# CPU_v1_0.net
KiCad netlist of a schematic drawn in EAGLE
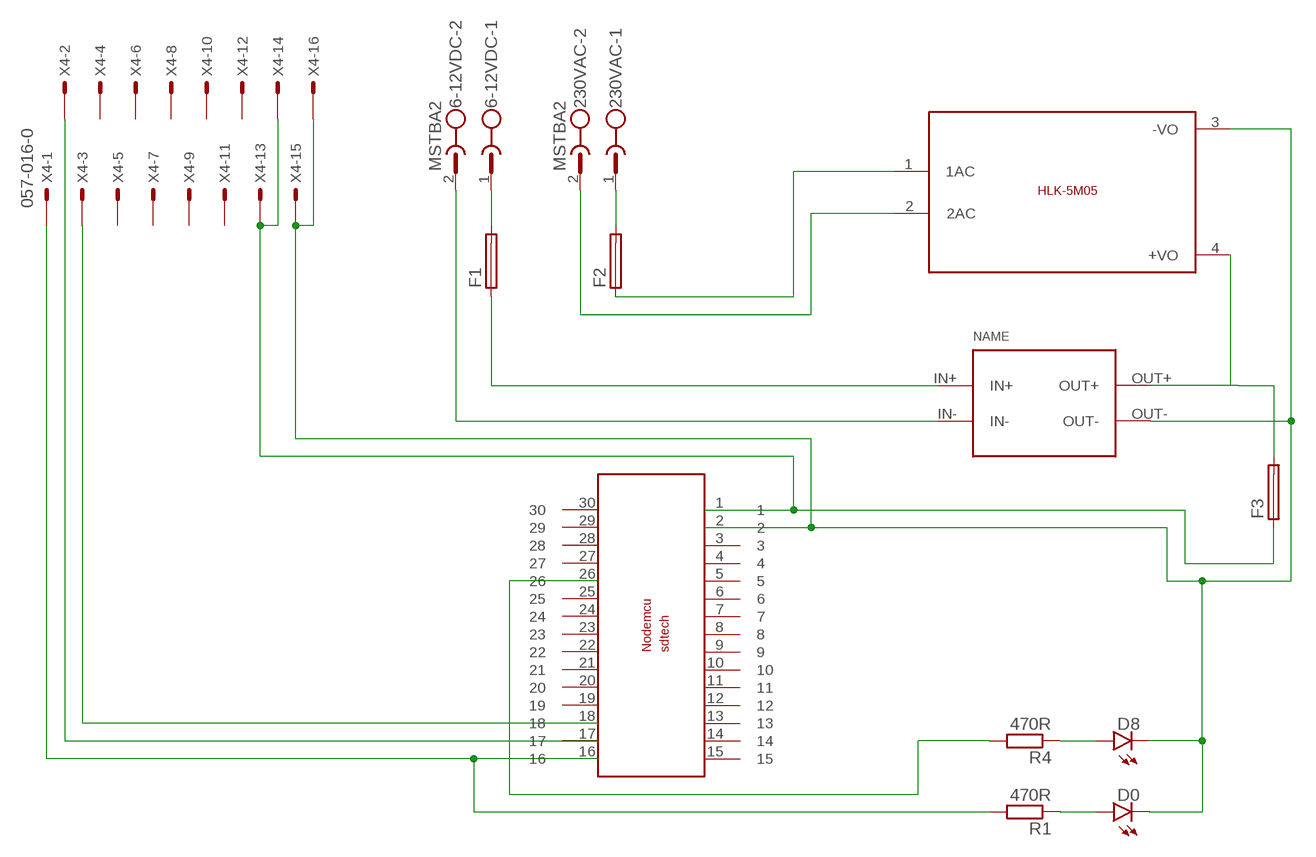
[diagram p0: schematic, sheet 1]

(export (version "E")
  (design (tool "Eeschema 10.0.6"))
  (components
    (comp (ref "6-12VDC")
      (value "MSTBA2")
      (footprint "eagle-import:MSTBA2")
      (fields (field (name "MF") "FARNELL") (field (name "MPN") "1757242"))
      (libsource (lib "eagle-import") (part "MSTBA2"))
    )
    (comp (ref "230VAC")
      (value "MSTBA2")
      (footprint "eagle-import:MSTBA2")
      (fields (field (name "MF") "FARNELL") (field (name "MPN") "1757242"))
      (libsource (lib "eagle-import") (part "MSTBA2"))
    )
    (comp (ref "D0")
      (value "LED3MM")
      (footprint "eagle-import:LED3MM")
      (libsource (lib "eagle-import") (part "LED3MM"))
    )
    (comp (ref "D8")
      (value "LED3MM")
      (footprint "eagle-import:LED3MM")
      (libsource (lib "eagle-import") (part "LED3MM"))
    )
    (comp (ref "F1")
      (value "SH22,5A")
      (footprint "eagle-import:SH22,5A")
      (fields (field (name "MPN") "0031.7701.11"))
      (libsource (lib "eagle-import") (part "SH22,5A"))
    )
    (comp (ref "F2")
      (value "SH22,5A")
      (footprint "eagle-import:SH22,5A")
      (fields (field (name "MPN") "0031.7701.11"))
      (libsource (lib "eagle-import") (part "SH22,5A"))
    )
    (comp (ref "F3")
      (value "SH22,5A")
      (footprint "eagle-import:SH22,5A")
      (fields (field (name "MPN") "0031.7701.11"))
      (libsource (lib "eagle-import") (part "SH22,5A"))
    )
    (comp (ref "R1")
      (value "470R")
      (footprint "eagle-import:0309_10")
      (libsource (lib "eagle-import") (part "R-EU_0309/10"))
    )
    (comp (ref "R4")
      (value "470R")
      (footprint "eagle-import:0309_10")
      (libsource (lib "eagle-import") (part "R-EU_0309/10"))
    )
    (comp (ref "U$1")
      (value "NODEMCUESP8266")
      (footprint "eagle-import:NODEMCUESP8266")
      (libsource (lib "eagle-import") (part "NODEMCUESP8266"))
    )
    (comp (ref "U$2")
      (value "CP8-ADJ")
      (footprint "eagle-import:CP8-ADJ")
      (libsource (lib "eagle-import") (part "CP8-ADJ"))
    )
    (comp (ref "U$3")
      (value "5VDC/5W")
      (footprint "eagle-import:HLK-5M05")
      (libsource (lib "eagle-import") (part "HLK-5M05"))
    )
    (comp (ref "X4")
      (value "057-016-0")
      (footprint "eagle-import:057-016-0")
      (libsource (lib "eagle-import") (part "057-016-0"))
    )
  )
  (nets
    (net (code "1") (name "Net-(6-12VDC-Pad1)") (class "Default")
      (node (ref "6-12VDC") (pin "1") (pinfunction "1_1") (pintype "passive"))
      (node (ref "F1") (pin "2") (pinfunction "2_2") (pintype "passive"))
    )
    (net (code "2") (name "Net-(6-12VDCB-1)") (class "Default")
      (node (ref "6-12VDC") (pin "2") (pinfunction "1_2") (pintype "passive"))
      (node (ref "U$2") (pin "IN-") (pinfunction "IN-_IN-") (pintype "passive"))
    )
    (net (code "3") (name "Net-(230VAC-Pad1)") (class "Default")
      (node (ref "230VAC") (pin "1") (pinfunction "1_1") (pintype "passive"))
      (node (ref "F2") (pin "2") (pinfunction "2_2") (pintype "passive"))
    )
    (net (code "4") (name "Net-(230VACB-1)") (class "Default")
      (node (ref "230VAC") (pin "2") (pinfunction "1_2") (pintype "passive"))
      (node (ref "U$3") (pin "2") (pinfunction "2AC_2") (pintype "bidirectional"))
    )
    (net (code "5") (name "Net-(D0-C)") (class "Default")
      (node (ref "D0") (pin "K") (pinfunction "C_K") (pintype "passive"))
      (node (ref "D8") (pin "K") (pinfunction "C_K") (pintype "passive"))
      (node (ref "U$1") (pin "2") (pinfunction "2_2") (pintype "bidirectional"))
      (node (ref "U$2") (pin "OUT-") (pinfunction "OUT-_OUT-") (pintype "passive"))
      (node (ref "U$3") (pin "3") (pinfunction "-VO_3") (pintype "bidirectional"))
      (node (ref "X4") (pin "15") (pinfunction "S_15") (pintype "passive"))
      (node (ref "X4") (pin "16") (pinfunction "S_16") (pintype "passive"))
    )
    (net (code "6") (name "Net-(D0-PadA)") (class "Default")
      (node (ref "D0") (pin "A") (pinfunction "A_A") (pintype "passive"))
      (node (ref "R1") (pin "1") (pinfunction "1_1") (pintype "passive"))
    )
    (net (code "7") (name "Net-(D8-PadA)") (class "Default")
      (node (ref "D8") (pin "A") (pinfunction "A_A") (pintype "passive"))
      (node (ref "R4") (pin "1") (pinfunction "1_1") (pintype "passive"))
    )
    (net (code "8") (name "Net-(F1-Pad1)") (class "Default")
      (node (ref "F1") (pin "1") (pinfunction "1_1") (pintype "passive"))
      (node (ref "U$2") (pin "IN+") (pinfunction "IN+_IN+") (pintype "passive"))
    )
    (net (code "9") (name "Net-(R4-Pad2)") (class "Default")
      (node (ref "R4") (pin "2") (pinfunction "2_2") (pintype "passive"))
      (node (ref "U$1") (pin "26") (pinfunction "26_26") (pintype "bidirectional"))
    )
    (net (code "10") (name "Net-(U$3-+VO)") (class "Default")
      (node (ref "F3") (pin "2") (pinfunction "2_2") (pintype "passive"))
      (node (ref "U$2") (pin "OUT+") (pinfunction "OUT+_OUT+") (pintype "passive"))
      (node (ref "U$3") (pin "4") (pinfunction "+VO_4") (pintype "bidirectional"))
    )
    (net (code "11") (name "Net-(U$3-1AC)") (class "Default")
      (node (ref "F2") (pin "1") (pinfunction "1_1") (pintype "passive"))
      (node (ref "U$3") (pin "1") (pinfunction "1AC_1") (pintype "bidirectional"))
    )
    (net (code "12") (name "Net-(X4A-S)") (class "Default")
      (node (ref "R1") (pin "2") (pinfunction "2_2") (pintype "passive"))
      (node (ref "U$1") (pin "16") (pinfunction "16_16") (pintype "bidirectional"))
      (node (ref "X4") (pin "1") (pinfunction "S_1") (pintype "passive"))
    )
    (net (code "13") (name "Net-(X4E-S)") (class "Default")
      (node (ref "F3") (pin "1") (pinfunction "1_1") (pintype "passive"))
      (node (ref "U$1") (pin "1") (pinfunction "1_1") (pintype "bidirectional"))
      (node (ref "X4") (pin "13") (pinfunction "S_13") (pintype "passive"))
      (node (ref "X4") (pin "14") (pinfunction "S_14") (pintype "passive"))
    )
    (net (code "14") (name "Net-(X4I-S)") (class "Default")
      (node (ref "U$1") (pin "17") (pinfunction "17_17") (pintype "bidirectional"))
      (node (ref "X4") (pin "2") (pinfunction "S_2") (pintype "passive"))
    )
    (net (code "15") (name "Net-(X4J-S)") (class "Default")
      (node (ref "U$1") (pin "18") (pinfunction "18_18") (pintype "bidirectional"))
      (node (ref "X4") (pin "3") (pinfunction "S_3") (pintype "passive"))
    )
    (net (code "16") (name "unconnected-(U$1-Pad3)") (class "Default")
      (node (ref "U$1") (pin "3") (pinfunction "3_3") (pintype "bidirectional"))
    )
    (net (code "17") (name "unconnected-(U$1-Pad4)") (class "Default")
      (node (ref "U$1") (pin "4") (pinfunction "4_4") (pintype "bidirectional"))
    )
    (net (code "18") (name "unconnected-(U$1-Pad5)") (class "Default")
      (node (ref "U$1") (pin "5") (pinfunction "5_5") (pintype "bidirectional"))
    )
    (net (code "19") (name "unconnected-(U$1-Pad6)") (class "Default")
      (node (ref "U$1") (pin "6") (pinfunction "6_6") (pintype "bidirectional"))
    )
    (net (code "20") (name "unconnected-(U$1-Pad7)") (class "Default")
      (node (ref "U$1") (pin "7") (pinfunction "7_7") (pintype "bidirectional"))
    )
    (net (code "21") (name "unconnected-(U$1-Pad8)") (class "Default")
      (node (ref "U$1") (pin "8") (pinfunction "8_8") (pintype "bidirectional"))
    )
    (net (code "22") (name "unconnected-(U$1-Pad9)") (class "Default")
      (node (ref "U$1") (pin "9") (pinfunction "9_9") (pintype "bidirectional"))
    )
    (net (code "23") (name "unconnected-(U$1-Pad10)") (class "Default")
      (node (ref "U$1") (pin "10") (pinfunction "10_10") (pintype "bidirectional"))
    )
    (net (code "24") (name "unconnected-(U$1-Pad11)") (class "Default")
      (node (ref "U$1") (pin "11") (pinfunction "11_11") (pintype "bidirectional"))
    )
    (net (code "25") (name "unconnected-(U$1-Pad12)") (class "Default")
      (node (ref "U$1") (pin "12") (pinfunction "12_12") (pintype "bidirectional"))
    )
    (net (code "26") (name "unconnected-(U$1-Pad13)") (class "Default")
      (node (ref "U$1") (pin "13") (pinfunction "13_13") (pintype "bidirectional"))
    )
    (net (code "27") (name "unconnected-(U$1-Pad14)") (class "Default")
      (node (ref "U$1") (pin "14") (pinfunction "14_14") (pintype "bidirectional"))
    )
    (net (code "28") (name "unconnected-(U$1-Pad15)") (class "Default")
      (node (ref "U$1") (pin "15") (pinfunction "15_15") (pintype "bidirectional"))
    )
    (net (code "29") (name "unconnected-(U$1-Pad19)") (class "Default")
      (node (ref "U$1") (pin "19") (pinfunction "19_19") (pintype "bidirectional"))
    )
    (net (code "30") (name "unconnected-(U$1-Pad20)") (class "Default")
      (node (ref "U$1") (pin "20") (pinfunction "20_20") (pintype "bidirectional"))
    )
    (net (code "31") (name "unconnected-(U$1-Pad21)") (class "Default")
      (node (ref "U$1") (pin "21") (pinfunction "21_21") (pintype "bidirectional"))
    )
    (net (code "32") (name "unconnected-(U$1-Pad22)") (class "Default")
      (node (ref "U$1") (pin "22") (pinfunction "22_22") (pintype "bidirectional"))
    )
    (net (code "33") (name "unconnected-(U$1-Pad23)") (class "Default")
      (node (ref "U$1") (pin "23") (pinfunction "23_23") (pintype "bidirectional"))
    )
    (net (code "34") (name "unconnected-(U$1-Pad24)") (class "Default")
      (node (ref "U$1") (pin "24") (pinfunction "24_24") (pintype "bidirectional"))
    )
    (net (code "35") (name "unconnected-(U$1-Pad25)") (class "Default")
      (node (ref "U$1") (pin "25") (pinfunction "25_25") (pintype "bidirectional"))
    )
    (net (code "36") (name "unconnected-(U$1-Pad27)") (class "Default")
      (node (ref "U$1") (pin "27") (pinfunction "27_27") (pintype "bidirectional"))
    )
    (net (code "37") (name "unconnected-(U$1-Pad28)") (class "Default")
      (node (ref "U$1") (pin "28") (pinfunction "28_28") (pintype "bidirectional"))
    )
    (net (code "38") (name "unconnected-(U$1-Pad29)") (class "Default")
      (node (ref "U$1") (pin "29") (pinfunction "29_29") (pintype "bidirectional"))
    )
    (net (code "39") (name "unconnected-(U$1-Pad30)") (class "Default")
      (node (ref "U$1") (pin "30") (pinfunction "30_30") (pintype "bidirectional"))
    )
    (net (code "40") (name "unconnected-(X4B-S-Pad10)") (class "Default")
      (node (ref "X4") (pin "10") (pinfunction "S_10") (pintype "passive"))
    )
    (net (code "41") (name "unconnected-(X4C-S-Pad11)") (class "Default")
      (node (ref "X4") (pin "11") (pinfunction "S_11") (pintype "passive"))
    )
    (net (code "42") (name "unconnected-(X4D-S-Pad12)") (class "Default")
      (node (ref "X4") (pin "12") (pinfunction "S_12") (pintype "passive"))
    )
    (net (code "43") (name "unconnected-(X4K-S-Pad4)") (class "Default")
      (node (ref "X4") (pin "4") (pinfunction "S_4") (pintype "passive"))
    )
    (net (code "44") (name "unconnected-(X4L-S-Pad5)") (class "Default")
      (node (ref "X4") (pin "5") (pinfunction "S_5") (pintype "passive"))
    )
    (net (code "45") (name "unconnected-(X4M-S-Pad6)") (class "Default")
      (node (ref "X4") (pin "6") (pinfunction "S_6") (pintype "passive"))
    )
    (net (code "46") (name "unconnected-(X4N-S-Pad7)") (class "Default")
      (node (ref "X4") (pin "7") (pinfunction "S_7") (pintype "passive"))
    )
    (net (code "47") (name "unconnected-(X4O-S-Pad8)") (class "Default")
      (node (ref "X4") (pin "8") (pinfunction "S_8") (pintype "passive"))
    )
    (net (code "48") (name "unconnected-(X4P-S-Pad9)") (class "Default")
      (node (ref "X4") (pin "9") (pinfunction "S_9") (pintype "passive"))
    )
  )
)
